# Throttle.net
KiCad netlist of a schematic drawn in EAGLE
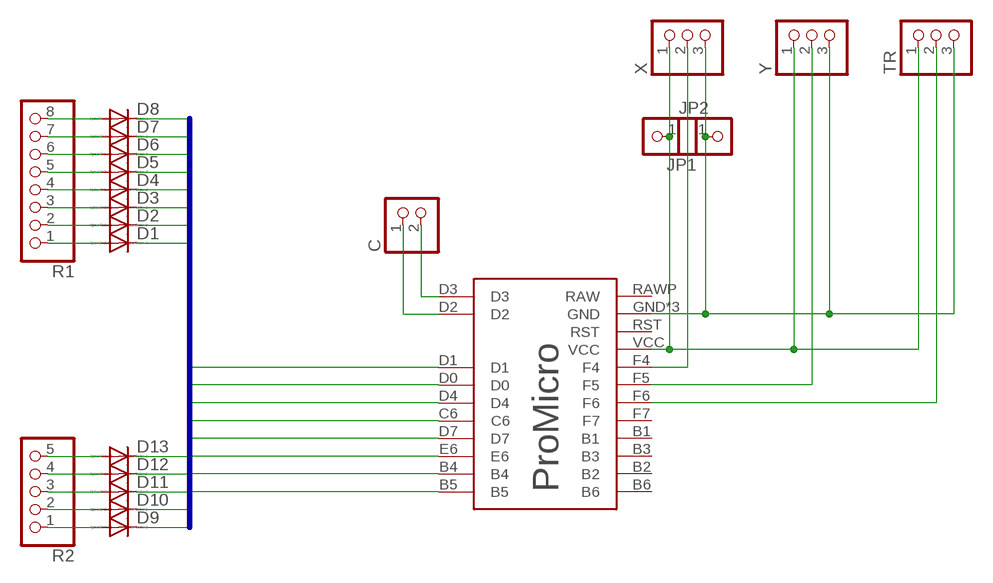
[diagram p0: schematic, sheet 1]

(export (version "E")
  (design (tool "Eeschema 10.0.6"))
  (components
    (comp (ref "C")
      (value "PINHD-1X2")
      (footprint "eagle-import:1X02")
      (libsource (lib "eagle-import") (part "PINHD-1X2"))
    )
    (comp (ref "D1")
      (value "DIODE-MINIMELF")
      (footprint "eagle-import:MINIMELF")
      (libsource (lib "eagle-import") (part "DIODE-MINIMELF"))
    )
    (comp (ref "D2")
      (value "DIODE-MINIMELF")
      (footprint "eagle-import:MINIMELF")
      (libsource (lib "eagle-import") (part "DIODE-MINIMELF"))
    )
    (comp (ref "D3")
      (value "DIODE-MINIMELF")
      (footprint "eagle-import:MINIMELF")
      (libsource (lib "eagle-import") (part "DIODE-MINIMELF"))
    )
    (comp (ref "D4")
      (value "DIODE-MINIMELF")
      (footprint "eagle-import:MINIMELF")
      (libsource (lib "eagle-import") (part "DIODE-MINIMELF"))
    )
    (comp (ref "D5")
      (value "DIODE-MINIMELF")
      (footprint "eagle-import:MINIMELF")
      (libsource (lib "eagle-import") (part "DIODE-MINIMELF"))
    )
    (comp (ref "D6")
      (value "DIODE-MINIMELF")
      (footprint "eagle-import:MINIMELF")
      (libsource (lib "eagle-import") (part "DIODE-MINIMELF"))
    )
    (comp (ref "D7")
      (value "DIODE-MINIMELF")
      (footprint "eagle-import:MINIMELF")
      (libsource (lib "eagle-import") (part "DIODE-MINIMELF"))
    )
    (comp (ref "D8")
      (value "DIODE-MINIMELF")
      (footprint "eagle-import:MINIMELF")
      (libsource (lib "eagle-import") (part "DIODE-MINIMELF"))
    )
    (comp (ref "D9")
      (value "DIODE-MINIMELF")
      (footprint "eagle-import:MINIMELF")
      (libsource (lib "eagle-import") (part "DIODE-MINIMELF"))
    )
    (comp (ref "D10")
      (value "DIODE-MINIMELF")
      (footprint "eagle-import:MINIMELF")
      (libsource (lib "eagle-import") (part "DIODE-MINIMELF"))
    )
    (comp (ref "D11")
      (value "DIODE-MINIMELF")
      (footprint "eagle-import:MINIMELF")
      (libsource (lib "eagle-import") (part "DIODE-MINIMELF"))
    )
    (comp (ref "D12")
      (value "DIODE-MINIMELF")
      (footprint "eagle-import:MINIMELF")
      (libsource (lib "eagle-import") (part "DIODE-MINIMELF"))
    )
    (comp (ref "D13")
      (value "DIODE-MINIMELF")
      (footprint "eagle-import:MINIMELF")
      (libsource (lib "eagle-import") (part "DIODE-MINIMELF"))
    )
    (comp (ref "JP1")
      (value "PINHD-1X1")
      (footprint "eagle-import:1X01")
      (libsource (lib "eagle-import") (part "PINHD-1X1"))
    )
    (comp (ref "JP2")
      (value "PINHD-1X1")
      (footprint "eagle-import:1X01")
      (libsource (lib "eagle-import") (part "PINHD-1X1"))
    )
    (comp (ref "R1")
      (value "PINHD-1X8")
      (footprint "eagle-import:1X08")
      (libsource (lib "eagle-import") (part "PINHD-1X8"))
    )
    (comp (ref "R2")
      (value "PINHD-1X5")
      (footprint "eagle-import:1X05")
      (libsource (lib "eagle-import") (part "PINHD-1X5"))
    )
    (comp (ref "TR")
      (value "PINHD-1X3")
      (footprint "eagle-import:1X03")
      (libsource (lib "eagle-import") (part "PINHD-1X3"))
    )
    (comp (ref "U$1")
      (value "SPARKFUN")
      (footprint "eagle-import:PRO-MICRO")
      (libsource (lib "eagle-import") (part "SPARKFUN"))
    )
    (comp (ref "X")
      (value "PINHD-1X3")
      (footprint "eagle-import:1X03")
      (libsource (lib "eagle-import") (part "PINHD-1X3"))
    )
    (comp (ref "Y")
      (value "PINHD-1X3")
      (footprint "eagle-import:1X03")
      (libsource (lib "eagle-import") (part "PINHD-1X3"))
    )
  )
  (nets
    (net (code "1") (name "/R1") (class "Default")
      (node (ref "D1") (pin "C") (pinfunction "C_C") (pintype "passive"))
      (node (ref "D9") (pin "C") (pinfunction "C_C") (pintype "passive"))
      (node (ref "U$1") (pin "B5") (pinfunction "B5_B5") (pintype "bidirectional"))
    )
    (net (code "2") (name "/R2") (class "Default")
      (node (ref "D10") (pin "C") (pinfunction "C_C") (pintype "passive"))
      (node (ref "D2") (pin "C") (pinfunction "C_C") (pintype "passive"))
      (node (ref "U$1") (pin "B4") (pinfunction "B4_B4") (pintype "bidirectional"))
    )
    (net (code "3") (name "/R3") (class "Default")
      (node (ref "D11") (pin "C") (pinfunction "C_C") (pintype "passive"))
      (node (ref "D3") (pin "C") (pinfunction "C_C") (pintype "passive"))
      (node (ref "U$1") (pin "E6") (pinfunction "E6_E6") (pintype "bidirectional"))
    )
    (net (code "4") (name "/R4") (class "Default")
      (node (ref "D12") (pin "C") (pinfunction "C_C") (pintype "passive"))
      (node (ref "D4") (pin "C") (pinfunction "C_C") (pintype "passive"))
      (node (ref "U$1") (pin "D7") (pinfunction "D7_D7") (pintype "bidirectional"))
    )
    (net (code "5") (name "/R5") (class "Default")
      (node (ref "D13") (pin "C") (pinfunction "C_C") (pintype "passive"))
      (node (ref "D5") (pin "C") (pinfunction "C_C") (pintype "passive"))
      (node (ref "U$1") (pin "C6") (pinfunction "C6_C6") (pintype "bidirectional"))
    )
    (net (code "6") (name "/R6") (class "Default")
      (node (ref "D6") (pin "C") (pinfunction "C_C") (pintype "passive"))
      (node (ref "U$1") (pin "D4") (pinfunction "D4_D4") (pintype "bidirectional"))
    )
    (net (code "7") (name "/R7") (class "Default")
      (node (ref "D7") (pin "C") (pinfunction "C_C") (pintype "passive"))
      (node (ref "U$1") (pin "D0") (pinfunction "D0_D0") (pintype "bidirectional"))
    )
    (net (code "8") (name "/R8") (class "Default")
      (node (ref "D8") (pin "C") (pinfunction "C_C") (pintype "passive"))
      (node (ref "U$1") (pin "D1") (pinfunction "D1_D1") (pintype "bidirectional"))
    )
    (net (code "9") (name "Net-(C-Pad1)") (class "Default")
      (node (ref "C") (pin "1") (pinfunction "1_1") (pintype "passive"))
      (node (ref "U$1") (pin "D2") (pinfunction "D2_D2") (pintype "bidirectional"))
    )
    (net (code "10") (name "Net-(C-Pad2)") (class "Default")
      (node (ref "C") (pin "2") (pinfunction "2_2") (pintype "passive"))
      (node (ref "U$1") (pin "D3") (pinfunction "D3_D3") (pintype "bidirectional"))
    )
    (net (code "11") (name "Net-(D1-PadA)") (class "Default")
      (node (ref "D1") (pin "A") (pinfunction "A_A") (pintype "passive"))
      (node (ref "R1") (pin "1") (pinfunction "1_1") (pintype "passive"))
    )
    (net (code "12") (name "Net-(D2-PadA)") (class "Default")
      (node (ref "D2") (pin "A") (pinfunction "A_A") (pintype "passive"))
      (node (ref "R1") (pin "2") (pinfunction "2_2") (pintype "passive"))
    )
    (net (code "13") (name "Net-(D3-PadA)") (class "Default")
      (node (ref "D3") (pin "A") (pinfunction "A_A") (pintype "passive"))
      (node (ref "R1") (pin "3") (pinfunction "3_3") (pintype "passive"))
    )
    (net (code "14") (name "Net-(D4-PadA)") (class "Default")
      (node (ref "D4") (pin "A") (pinfunction "A_A") (pintype "passive"))
      (node (ref "R1") (pin "4") (pinfunction "4_4") (pintype "passive"))
    )
    (net (code "15") (name "Net-(D5-PadA)") (class "Default")
      (node (ref "D5") (pin "A") (pinfunction "A_A") (pintype "passive"))
      (node (ref "R1") (pin "5") (pinfunction "5_5") (pintype "passive"))
    )
    (net (code "16") (name "Net-(D6-PadA)") (class "Default")
      (node (ref "D6") (pin "A") (pinfunction "A_A") (pintype "passive"))
      (node (ref "R1") (pin "6") (pinfunction "6_6") (pintype "passive"))
    )
    (net (code "17") (name "Net-(D7-PadA)") (class "Default")
      (node (ref "D7") (pin "A") (pinfunction "A_A") (pintype "passive"))
      (node (ref "R1") (pin "7") (pinfunction "7_7") (pintype "passive"))
    )
    (net (code "18") (name "Net-(D8-PadA)") (class "Default")
      (node (ref "D8") (pin "A") (pinfunction "A_A") (pintype "passive"))
      (node (ref "R1") (pin "8") (pinfunction "8_8") (pintype "passive"))
    )
    (net (code "19") (name "Net-(D9-PadA)") (class "Default")
      (node (ref "D9") (pin "A") (pinfunction "A_A") (pintype "passive"))
      (node (ref "R2") (pin "1") (pinfunction "1_1") (pintype "passive"))
    )
    (net (code "20") (name "Net-(D10-PadA)") (class "Default")
      (node (ref "D10") (pin "A") (pinfunction "A_A") (pintype "passive"))
      (node (ref "R2") (pin "2") (pinfunction "2_2") (pintype "passive"))
    )
    (net (code "21") (name "Net-(D11-PadA)") (class "Default")
      (node (ref "D11") (pin "A") (pinfunction "A_A") (pintype "passive"))
      (node (ref "R2") (pin "3") (pinfunction "3_3") (pintype "passive"))
    )
    (net (code "22") (name "Net-(D12-PadA)") (class "Default")
      (node (ref "D12") (pin "A") (pinfunction "A_A") (pintype "passive"))
      (node (ref "R2") (pin "4") (pinfunction "4_4") (pintype "passive"))
    )
    (net (code "23") (name "Net-(D13-PadA)") (class "Default")
      (node (ref "D13") (pin "A") (pinfunction "A_A") (pintype "passive"))
      (node (ref "R2") (pin "5") (pinfunction "5_5") (pintype "passive"))
    )
    (net (code "24") (name "Net-(JP1-Pad1)") (class "Default")
      (node (ref "JP1") (pin "1") (pinfunction "1_1") (pintype "passive"))
      (node (ref "TR") (pin "1") (pinfunction "1_1") (pintype "passive"))
      (node (ref "U$1") (pin "VCC") (pinfunction "VCC_VCC") (pintype "bidirectional"))
      (node (ref "X") (pin "1") (pinfunction "1_1") (pintype "passive"))
      (node (ref "Y") (pin "1") (pinfunction "1_1") (pintype "passive"))
    )
    (net (code "25") (name "Net-(JP2-Pad1)") (class "Default")
      (node (ref "JP2") (pin "1") (pinfunction "1_1") (pintype "passive"))
      (node (ref "TR") (pin "3") (pinfunction "3_3") (pintype "passive"))
      (node (ref "U$1") (pin "GND") (pinfunction "GND_GND") (pintype "bidirectional"))
      (node (ref "U$1") (pin "GND3") (pinfunction "GND_GND3") (pintype "bidirectional"))
      (node (ref "U$1") (pin "GND4") (pinfunction "GND_GND4") (pintype "bidirectional"))
      (node (ref "X") (pin "3") (pinfunction "3_3") (pintype "passive"))
      (node (ref "Y") (pin "3") (pinfunction "3_3") (pintype "passive"))
    )
    (net (code "26") (name "Net-(TR-Pad2)") (class "Default")
      (node (ref "TR") (pin "2") (pinfunction "2_2") (pintype "passive"))
      (node (ref "U$1") (pin "F6") (pinfunction "F6_F6") (pintype "bidirectional"))
    )
    (net (code "27") (name "Net-(U$1-PadF4)") (class "Default")
      (node (ref "U$1") (pin "F4") (pinfunction "F4_F4") (pintype "bidirectional"))
      (node (ref "X") (pin "2") (pinfunction "2_2") (pintype "passive"))
    )
    (net (code "28") (name "Net-(U$1-PadF5)") (class "Default")
      (node (ref "U$1") (pin "F5") (pinfunction "F5_F5") (pintype "bidirectional"))
      (node (ref "Y") (pin "2") (pinfunction "2_2") (pintype "passive"))
    )
    (net (code "29") (name "unconnected-(U$1-PadB1)") (class "Default")
      (node (ref "U$1") (pin "B1") (pinfunction "B1_B1") (pintype "bidirectional"))
    )
    (net (code "30") (name "unconnected-(U$1-PadB2)") (class "Default")
      (node (ref "U$1") (pin "B2") (pinfunction "B2_B2") (pintype "bidirectional"))
    )
    (net (code "31") (name "unconnected-(U$1-PadB3)") (class "Default")
      (node (ref "U$1") (pin "B3") (pinfunction "B3_B3") (pintype "bidirectional"))
    )
    (net (code "32") (name "unconnected-(U$1-PadB6)") (class "Default")
      (node (ref "U$1") (pin "B6") (pinfunction "B6_B6") (pintype "bidirectional"))
    )
    (net (code "33") (name "unconnected-(U$1-PadF7)") (class "Default")
      (node (ref "U$1") (pin "F7") (pinfunction "F7_F7") (pintype "bidirectional"))
    )
    (net (code "34") (name "unconnected-(U$1-PadRST)") (class "Default")
      (node (ref "U$1") (pin "RST") (pinfunction "RST_RST") (pintype "bidirectional"))
    )
    (net (code "35") (name "unconnected-(U$1-RAW-PadRAWP)") (class "Default")
      (node (ref "U$1") (pin "RAWP") (pinfunction "RAW_RAWP") (pintype "bidirectional"))
    )
  )
)
